# 485.net
KiCad netlist of a schematic drawn in Altium Designer
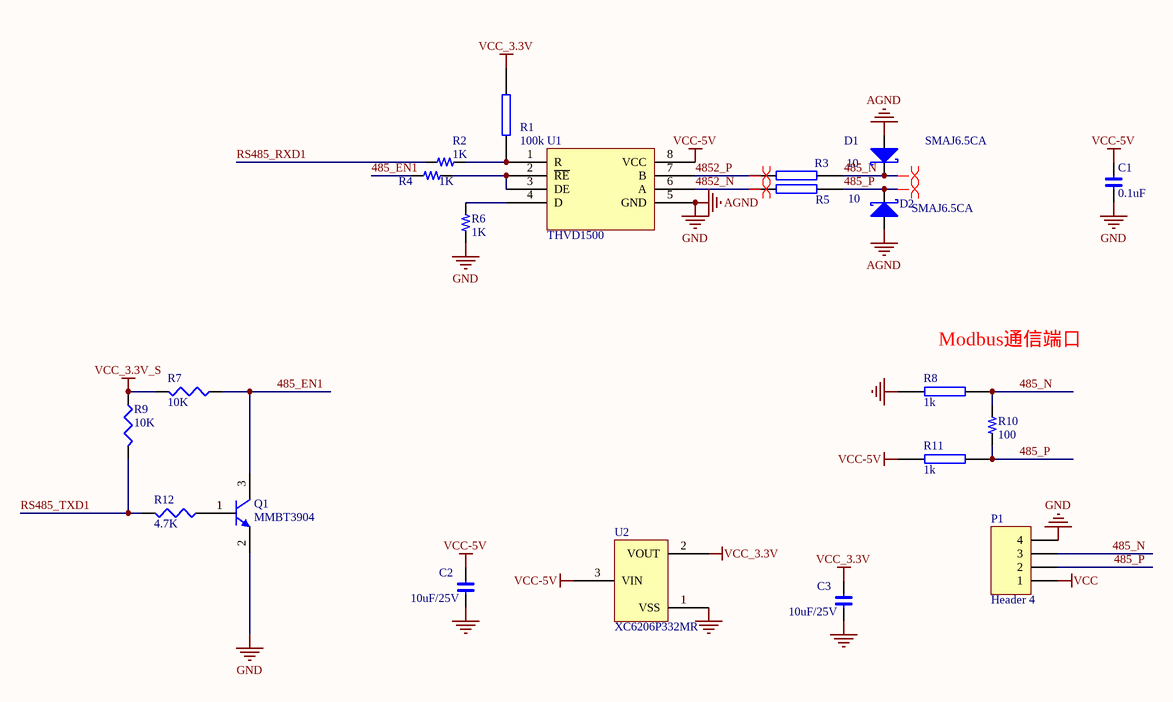
[diagram p0: 485.SchDoc]

(export (version "E")
  (design (tool "Eeschema 10.0.6"))
  (components
    (comp (ref "C1")
      (value "0.1uF")
      (footprint "0603C")
      (description "C")
      (libsource (lib "Schlib_20110825") (part "C"))
    )
    (comp (ref "C2")
      (value "10uF/25V")
      (footprint "0603C")
      (description "C")
      (libsource (lib "Schlib_20110825") (part "C"))
    )
    (comp (ref "C3")
      (value "10uF/25V")
      (footprint "0603C")
      (description "C")
      (libsource (lib "Schlib_20110825") (part "C"))
    )
    (comp (ref "D1")
      (value "SMAJ6.5CA")
      (footprint "SMA")
      (description "Schottky Diode")
      (libsource (lib "*") (part "DIODE S"))
    )
    (comp (ref "D2")
      (value "SMAJ6.5CA")
      (footprint "SMA")
      (description "Schottky Diode")
      (libsource (lib "*") (part "DIODE S"))
    )
    (comp (ref "P1")
      (value "Header 4")
      (footprint "4X2.54MMZ")
      (description "Header, 4-Pin")
      (fields (field (name "PUBLISHER") "Altium Limited"))
      (libsource (lib "Miscellaneous Connectors") (part "Header 4"))
    )
    (comp (ref "Q1") (value "MMBT3904") (footprint "SOT23-3") (libsource (lib "Schlib1") (part "NPN")))
    (comp (ref "R1") (value "100k") (footprint "0603R") (libsource (lib "") (part "RES2_1")))
    (comp (ref "R2") (value "1K") (footprint "0603R") (description "R") (libsource (lib "JRJ_1") (part "R")))
    (comp (ref "R3") (value "10") (footprint "1206R") (libsource (lib "") (part "RES2_1")))
    (comp (ref "R4") (value "1K") (footprint "0603R") (description "R") (libsource (lib "JRJ_1") (part "R")))
    (comp (ref "R5") (value "10") (footprint "1206R") (libsource (lib "") (part "RES2_1")))
    (comp (ref "R6") (value "1K") (footprint "0603R") (description "R") (libsource (lib "JRJ_1") (part "R")))
    (comp (ref "R7")
      (value "10K")
      (footprint "0603R")
      (libsource (lib "ZWLIntegrated_Library") (part "RES1"))
    )
    (comp (ref "R8") (value "1k") (footprint "0603R") (libsource (lib "*") (part "RES2")))
    (comp (ref "R9")
      (value "10K")
      (footprint "0603R")
      (libsource (lib "ZWLIntegrated_Library") (part "RES1"))
    )
    (comp (ref "R10")
      (value "100")
      (footprint "0603R")
      (description "R")
      (libsource (lib "JRJ_1") (part "R"))
    )
    (comp (ref "R11") (value "1k") (footprint "0603R") (libsource (lib "*") (part "RES2")))
    (comp (ref "R12")
      (value "4.7K")
      (footprint "0603R")
      (libsource (lib "ZWLIntegrated_Library") (part "RES1"))
    )
    (comp (ref "U1") (value "THVD1500") (footprint "so-8") (libsource (lib "Schlib1") (part "SN65HVD06D")))
    (comp (ref "U2")
      (value "XC6206P332MR")
      (footprint "SOT23-3")
      (libsource (lib "stm32") (part "XC6206P302MR"))
    )
  )
  (nets
    (net (code "1") (name "/485_EN1") (class "Default")
      (node (ref "Q1") (pin "3") (pinfunction "C_3") (pintype "passive"))
      (node (ref "R4") (pin "2") (pintype "passive"))
      (node (ref "R7") (pin "1") (pinfunction "1_1") (pintype "passive"))
    )
    (net (code "2") (name "/485_N") (class "Default")
      (node (ref "D1") (pin "2") (pinfunction "K_2") (pintype "passive"))
      (node (ref "P1") (pin "3") (pinfunction "3_3") (pintype "passive"))
      (node (ref "R10") (pin "2") (pintype "passive"))
      (node (ref "R3") (pin "1") (pinfunction "1_1") (pintype "passive"))
      (node (ref "R8") (pin "1") (pinfunction "1_1") (pintype "passive"))
    )
    (net (code "3") (name "/485_P") (class "Default")
      (node (ref "D2") (pin "2") (pinfunction "K_2") (pintype "passive"))
      (node (ref "P1") (pin "2") (pinfunction "2_2") (pintype "passive"))
      (node (ref "R10") (pin "1") (pintype "passive"))
      (node (ref "R11") (pin "2") (pinfunction "2_2") (pintype "passive"))
      (node (ref "R5") (pin "1") (pinfunction "1_1") (pintype "passive"))
    )
    (net (code "4") (name "/4852_N") (class "Default")
      (node (ref "R5") (pin "2") (pinfunction "2_2") (pintype "passive"))
      (node (ref "U1") (pin "6") (pinfunction "A_6") (pintype "passive"))
    )
    (net (code "5") (name "/4852_P") (class "Default")
      (node (ref "R3") (pin "2") (pinfunction "2_2") (pintype "passive"))
      (node (ref "U1") (pin "7") (pinfunction "B_7") (pintype "passive"))
    )
    (net (code "6") (name "/RS485_RXD1") (class "Default") (node (ref "R2") (pin "2") (pintype "passive")))
    (net (code "7") (name "/RS485_TXD1") (class "Default")
      (node (ref "R12") (pin "2") (pinfunction "2_2") (pintype "passive"))
      (node (ref "R9") (pin "2") (pinfunction "2_2") (pintype "passive"))
    )
    (net (code "8") (name "AGND") (class "Default")
      (node (ref "C1") (pin "1") (pintype "passive"))
      (node (ref "C2") (pin "1") (pintype "passive"))
      (node (ref "C3") (pin "1") (pintype "passive"))
      (node (ref "D1") (pin "1") (pinfunction "A_1") (pintype "passive"))
      (node (ref "D2") (pin "1") (pinfunction "A_1") (pintype "passive"))
      (node (ref "P1") (pin "4") (pinfunction "4_4") (pintype "passive"))
      (node (ref "Q1") (pin "2") (pinfunction "E_2") (pintype "passive"))
      (node (ref "R6") (pin "2") (pintype "passive"))
      (node (ref "R8") (pin "2") (pinfunction "2_2") (pintype "passive"))
      (node (ref "U1") (pin "5") (pinfunction "GND_5") (pintype "passive"))
      (node (ref "U2") (pin "1") (pinfunction "VSS_1") (pintype "passive"))
    )
    (net (code "9") (name "Net-(Q1-B)") (class "Default")
      (node (ref "Q1") (pin "1") (pinfunction "B_1") (pintype "passive"))
      (node (ref "R12") (pin "1") (pinfunction "1_1") (pintype "passive"))
    )
    (net (code "10") (name "Net-(U1-D)") (class "Default")
      (node (ref "R6") (pin "1") (pintype "passive"))
      (node (ref "U1") (pin "4") (pinfunction "D_4") (pintype "passive"))
    )
    (net (code "11") (name "Net-(U1-DE)") (class "Default")
      (node (ref "R4") (pin "1") (pintype "passive"))
      (node (ref "U1") (pin "2") (pinfunction "~{RE}_2") (pintype "passive"))
      (node (ref "U1") (pin "3") (pinfunction "DE_3") (pintype "passive"))
    )
    (net (code "12") (name "Net-(U1-R)") (class "Default")
      (node (ref "R1") (pin "1") (pinfunction "1_1") (pintype "passive"))
      (node (ref "R2") (pin "1") (pintype "passive"))
      (node (ref "U1") (pin "1") (pinfunction "R_1") (pintype "passive"))
    )
    (net (code "13") (name "VCC") (class "Default")
      (node (ref "P1") (pin "1") (pinfunction "1_1") (pintype "passive"))
    )
    (net (code "14") (name "VCC-5V") (class "Default")
      (node (ref "C1") (pin "2") (pintype "passive"))
      (node (ref "C2") (pin "2") (pintype "passive"))
      (node (ref "R11") (pin "1") (pinfunction "1_1") (pintype "passive"))
      (node (ref "U1") (pin "8") (pinfunction "VCC_8") (pintype "passive"))
      (node (ref "U2") (pin "3") (pinfunction "VIN_3") (pintype "passive"))
    )
    (net (code "15") (name "VCC_3.3V") (class "Default")
      (node (ref "C3") (pin "2") (pintype "passive"))
      (node (ref "R1") (pin "2") (pinfunction "2_2") (pintype "passive"))
      (node (ref "U2") (pin "2") (pinfunction "VOUT_2") (pintype "passive"))
    )
    (net (code "16") (name "VCC_3.3V_S") (class "Default")
      (node (ref "R7") (pin "2") (pinfunction "2_2") (pintype "passive"))
      (node (ref "R9") (pin "1") (pinfunction "1_1") (pintype "passive"))
    )
  )
)
